# Amplifier2ch.net
KiCad netlist of a schematic drawn in Altium Designer
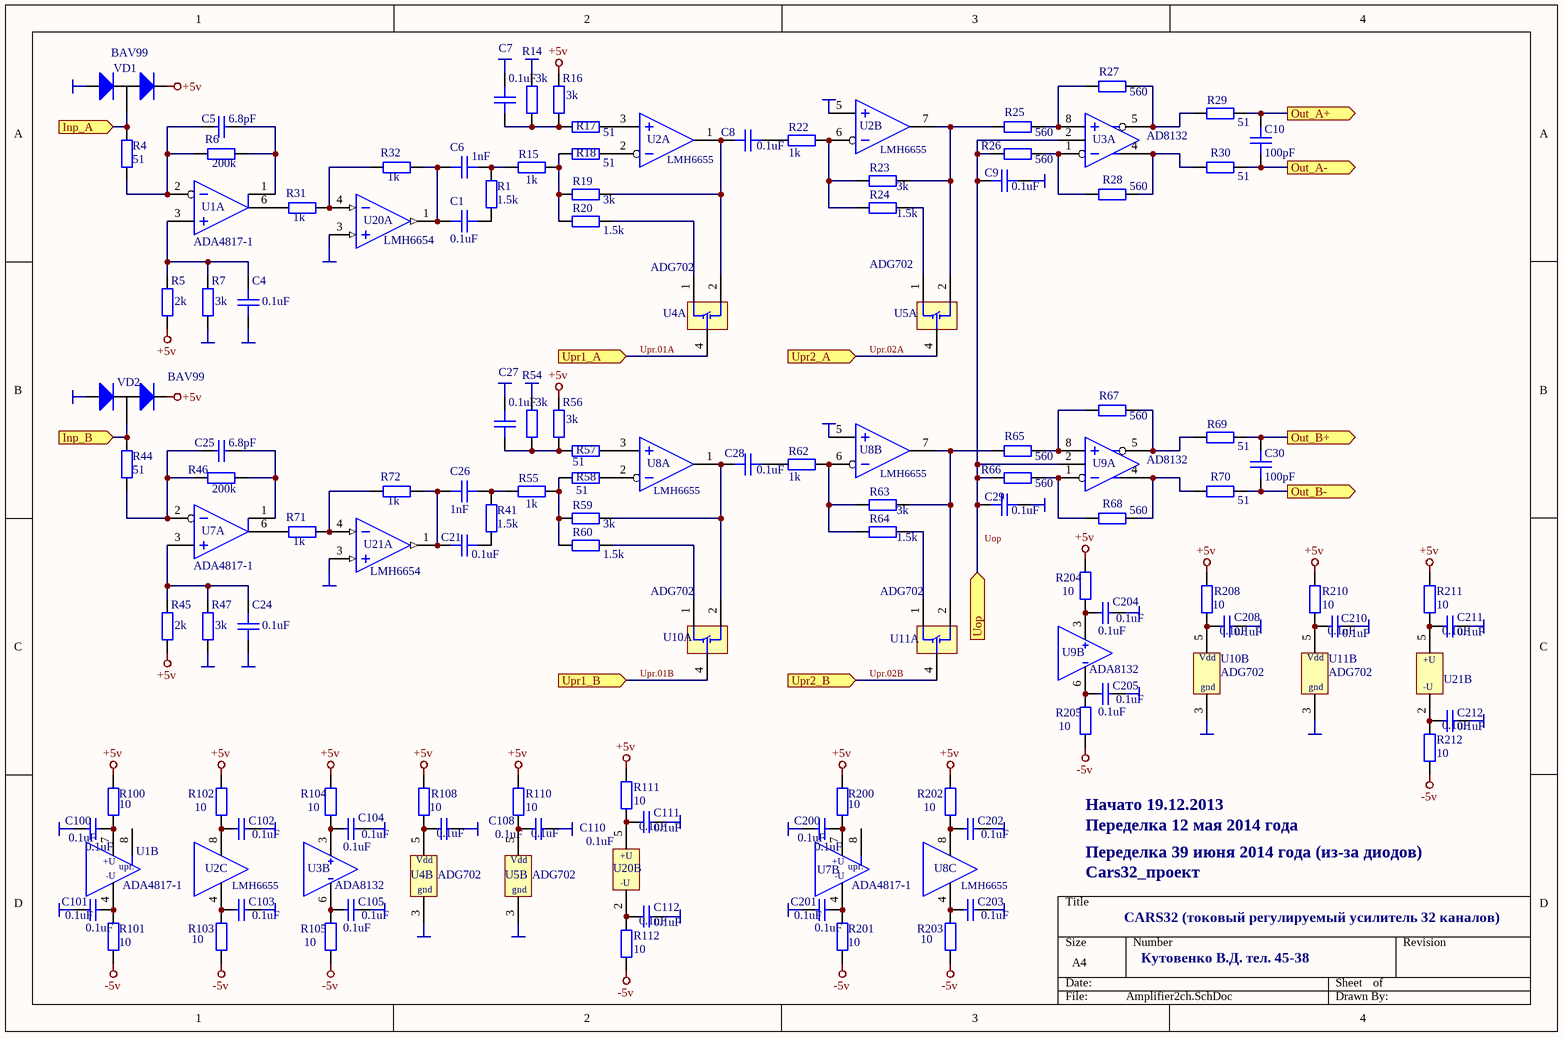
[diagram p0: Amplifier2ch.SchDoc]

(export (version "E")
  (design (tool "Eeschema 10.0.6"))
  (components
    (comp (ref "C1") (value "0.1uF") (footprint "0603") (libsource (lib "Kut") (part "C")))
    (comp (ref "C4") (value "0.1uF") (footprint "0603") (libsource (lib "Kut") (part "C")))
    (comp (ref "C5")
      (value "6.8pF")
      (footprint "0603")
      (description "Capacitor")
      (fields (field (name "PUBLISHER") "Altium Limited"))
      (libsource (lib "Miscellaneous Devices") (part "Cap"))
    )
    (comp (ref "C6") (value "1nF") (footprint "0603") (libsource (lib "Kut") (part "C")))
    (comp (ref "C7") (value "0.1uF") (footprint "0603") (libsource (lib "Kut") (part "C")))
    (comp (ref "C8") (value "0.1uF") (footprint "0603") (libsource (lib "Kut") (part "C")))
    (comp (ref "C9") (value "0.1uF") (footprint "0603") (libsource (lib "Kut") (part "C")))
    (comp (ref "C10") (value "100pF") (footprint "0603") (libsource (lib "Kut") (part "C")))
    (comp (ref "C21") (value "0.1uF") (footprint "0603") (libsource (lib "Kut") (part "C")))
    (comp (ref "C24") (value "0.1uF") (footprint "0603") (libsource (lib "Kut") (part "C")))
    (comp (ref "C25")
      (value "6.8pF")
      (footprint "0603")
      (description "Capacitor")
      (fields (field (name "PUBLISHER") "Altium Limited"))
      (libsource (lib "Miscellaneous Devices") (part "Cap"))
    )
    (comp (ref "C26") (value "1nF") (footprint "0603") (libsource (lib "Kut") (part "C")))
    (comp (ref "C27") (value "0.1uF") (footprint "0603") (libsource (lib "Kut") (part "C")))
    (comp (ref "C28") (value "0.1uF") (footprint "0603") (libsource (lib "Kut") (part "C")))
    (comp (ref "C29") (value "0.1uF") (footprint "0603") (libsource (lib "Kut") (part "C")))
    (comp (ref "C30") (value "100pF") (footprint "0603") (libsource (lib "Kut") (part "C")))
    (comp (ref "C100")
      (value "0.1uF")
      (footprint "0603")
      (description "Capacitor")
      (fields (field (name "ALTIUM_VALUE") "0.1uF") (field (name "PUBLISHER") "Altium Limited"))
      (libsource (lib "Miscellaneous Devices") (part "Cap"))
    )
    (comp (ref "C101")
      (value "0.1uF")
      (footprint "0603")
      (description "Capacitor")
      (fields (field (name "ALTIUM_VALUE") "0.1uF") (field (name "PUBLISHER") "Altium Limited"))
      (libsource (lib "Miscellaneous Devices") (part "Cap"))
    )
    (comp (ref "C102")
      (value "0.1uF")
      (footprint "0603")
      (description "Capacitor")
      (fields (field (name "PUBLISHER") "Altium Limited"))
      (libsource (lib "Miscellaneous Devices") (part "Cap"))
    )
    (comp (ref "C103")
      (value "0.1uF")
      (footprint "0603")
      (description "Capacitor")
      (fields (field (name "PUBLISHER") "Altium Limited"))
      (libsource (lib "Miscellaneous Devices") (part "Cap"))
    )
    (comp (ref "C104")
      (value "0.1uF")
      (footprint "0603")
      (description "Capacitor")
      (fields (field (name "ALTIUM_VALUE") "0.1uF") (field (name "PUBLISHER") "Altium Limited"))
      (libsource (lib "Miscellaneous Devices") (part "Cap"))
    )
    (comp (ref "C105")
      (value "0.1uF")
      (footprint "0603")
      (description "Capacitor")
      (fields (field (name "ALTIUM_VALUE") "0.1uF") (field (name "PUBLISHER") "Altium Limited"))
      (libsource (lib "Miscellaneous Devices") (part "Cap"))
    )
    (comp (ref "C108")
      (value "0.1uF")
      (footprint "0603")
      (description "Capacitor")
      (fields (field (name "ALTIUM_VALUE") "0.1uF") (field (name "PUBLISHER") "Altium Limited"))
      (libsource (lib "Miscellaneous Devices") (part "Cap"))
    )
    (comp (ref "C110")
      (value "0.1uF")
      (footprint "0603")
      (description "Capacitor")
      (fields (field (name "ALTIUM_VALUE") "0.1uF") (field (name "PUBLISHER") "Altium Limited"))
      (libsource (lib "Miscellaneous Devices") (part "Cap"))
    )
    (comp (ref "C111")
      (value "0.1uF")
      (footprint "0603")
      (description "Capacitor")
      (fields (field (name "ALTIUM_VALUE") "0.1uF") (field (name "PUBLISHER") "Altium Limited"))
      (libsource (lib "Miscellaneous Devices") (part "Cap"))
    )
    (comp (ref "C112")
      (value "0.1uF")
      (footprint "0603")
      (description "Capacitor")
      (fields (field (name "ALTIUM_VALUE") "0.1uF") (field (name "PUBLISHER") "Altium Limited"))
      (libsource (lib "Miscellaneous Devices") (part "Cap"))
    )
    (comp (ref "C200")
      (value "0.1uF")
      (footprint "0603")
      (description "Capacitor")
      (fields (field (name "ALTIUM_VALUE") "0.1uF") (field (name "PUBLISHER") "Altium Limited"))
      (libsource (lib "Miscellaneous Devices") (part "Cap"))
    )
    (comp (ref "C201")
      (value "0.1uF")
      (footprint "0603")
      (description "Capacitor")
      (fields (field (name "ALTIUM_VALUE") "0.1uF") (field (name "PUBLISHER") "Altium Limited"))
      (libsource (lib "Miscellaneous Devices") (part "Cap"))
    )
    (comp (ref "C202")
      (value "0.1uF")
      (footprint "0603")
      (description "Capacitor")
      (fields (field (name "PUBLISHER") "Altium Limited"))
      (libsource (lib "Miscellaneous Devices") (part "Cap"))
    )
    (comp (ref "C203")
      (value "0.1uF")
      (footprint "0603")
      (description "Capacitor")
      (fields (field (name "PUBLISHER") "Altium Limited"))
      (libsource (lib "Miscellaneous Devices") (part "Cap"))
    )
    (comp (ref "C204")
      (value "0.1uF")
      (footprint "0603")
      (description "Capacitor")
      (fields (field (name "ALTIUM_VALUE") "0.1uF") (field (name "PUBLISHER") "Altium Limited"))
      (libsource (lib "Miscellaneous Devices") (part "Cap"))
    )
    (comp (ref "C205")
      (value "0.1uF")
      (footprint "0603")
      (description "Capacitor")
      (fields (field (name "ALTIUM_VALUE") "0.1uF") (field (name "PUBLISHER") "Altium Limited"))
      (libsource (lib "Miscellaneous Devices") (part "Cap"))
    )
    (comp (ref "C208")
      (value "0.1uF")
      (footprint "0603")
      (description "Capacitor")
      (fields (field (name "ALTIUM_VALUE") "0.1uF") (field (name "PUBLISHER") "Altium Limited"))
      (libsource (lib "Miscellaneous Devices") (part "Cap"))
    )
    (comp (ref "C210")
      (value "0.1uF")
      (footprint "0603")
      (description "Capacitor")
      (fields (field (name "ALTIUM_VALUE") "0.1uF") (field (name "PUBLISHER") "Altium Limited"))
      (libsource (lib "Miscellaneous Devices") (part "Cap"))
    )
    (comp (ref "C211")
      (value "0.1uF")
      (footprint "0603")
      (description "Capacitor")
      (fields (field (name "ALTIUM_VALUE") "0.1uF") (field (name "PUBLISHER") "Altium Limited"))
      (libsource (lib "Miscellaneous Devices") (part "Cap"))
    )
    (comp (ref "C212")
      (value "0.1uF")
      (footprint "0603")
      (description "Capacitor")
      (fields (field (name "ALTIUM_VALUE") "0.1uF") (field (name "PUBLISHER") "Altium Limited"))
      (libsource (lib "Miscellaneous Devices") (part "Cap"))
    )
    (comp (ref "R1")
      (value "1.5k")
      (footprint "0603")
      (description "Resistor")
      (fields (field (name "PUBLISHER") "Altium Limited"))
      (libsource (lib "") (part "Res2_2"))
    )
    (comp (ref "R4")
      (value "51")
      (footprint "0603")
      (description "Resistor")
      (fields (field (name "PUBLISHER") "Altium Limited"))
      (libsource (lib "") (part "Res2_2"))
    )
    (comp (ref "R5")
      (value "2k")
      (footprint "0603")
      (description "Resistor")
      (fields (field (name "PUBLISHER") "Altium Limited"))
      (libsource (lib "") (part "Res2_2"))
    )
    (comp (ref "R6")
      (value "200k")
      (footprint "0603")
      (description "Resistor")
      (fields (field (name "PUBLISHER") "Altium Limited"))
      (libsource (lib "Miscellaneous Devices") (part "Res2"))
    )
    (comp (ref "R7")
      (value "3k")
      (footprint "0603")
      (description "Resistor")
      (fields (field (name "PUBLISHER") "Altium Limited"))
      (libsource (lib "") (part "Res2_1"))
    )
    (comp (ref "R14")
      (value "3k")
      (footprint "0603")
      (description "Resistor")
      (fields (field (name "PUBLISHER") "Altium Limited"))
      (libsource (lib "") (part "Res2_1"))
    )
    (comp (ref "R15")
      (value "1k")
      (footprint "0603")
      (description "Resistor")
      (fields (field (name "PUBLISHER") "Altium Limited"))
      (libsource (lib "Miscellaneous Devices") (part "Res2"))
    )
    (comp (ref "R16")
      (value "3k")
      (footprint "0603")
      (description "Resistor")
      (fields (field (name "PUBLISHER") "Altium Limited"))
      (libsource (lib "") (part "Res2_1"))
    )
    (comp (ref "R17")
      (value "51")
      (footprint "0603")
      (description "Resistor")
      (fields (field (name "PUBLISHER") "Altium Limited"))
      (libsource (lib "Miscellaneous Devices") (part "Res2"))
    )
    (comp (ref "R18")
      (value "51")
      (footprint "0603")
      (description "Resistor")
      (fields (field (name "PUBLISHER") "Altium Limited"))
      (libsource (lib "Miscellaneous Devices") (part "Res2"))
    )
    (comp (ref "R19")
      (value "3k")
      (footprint "0603")
      (description "Resistor")
      (fields (field (name "PUBLISHER") "Altium Limited"))
      (libsource (lib "Miscellaneous Devices") (part "Res2"))
    )
    (comp (ref "R20")
      (value "1.5k")
      (footprint "0603")
      (description "Resistor")
      (fields (field (name "PUBLISHER") "Altium Limited"))
      (libsource (lib "Miscellaneous Devices") (part "Res2"))
    )
    (comp (ref "R22")
      (value "1k")
      (footprint "0603")
      (description "Resistor")
      (fields (field (name "PUBLISHER") "Altium Limited"))
      (libsource (lib "Miscellaneous Devices") (part "Res2"))
    )
    (comp (ref "R23")
      (value "3k")
      (footprint "0603")
      (description "Resistor")
      (fields (field (name "PUBLISHER") "Altium Limited"))
      (libsource (lib "Miscellaneous Devices") (part "Res2"))
    )
    (comp (ref "R24")
      (value "1.5k")
      (footprint "0603")
      (description "Resistor")
      (fields (field (name "PUBLISHER") "Altium Limited"))
      (libsource (lib "Miscellaneous Devices") (part "Res2"))
    )
    (comp (ref "R25")
      (value "560")
      (footprint "0603")
      (description "Resistor")
      (fields (field (name "PUBLISHER") "Altium Limited"))
      (libsource (lib "Miscellaneous Devices") (part "Res2"))
    )
    (comp (ref "R26")
      (value "560")
      (footprint "0603")
      (description "Resistor")
      (fields (field (name "PUBLISHER") "Altium Limited"))
      (libsource (lib "Miscellaneous Devices") (part "Res2"))
    )
    (comp (ref "R27")
      (value "560")
      (footprint "0603")
      (description "Resistor")
      (fields (field (name "PUBLISHER") "Altium Limited"))
      (libsource (lib "Miscellaneous Devices") (part "Res2"))
    )
    (comp (ref "R28")
      (value "560")
      (footprint "0603")
      (description "Resistor")
      (fields (field (name "PUBLISHER") "Altium Limited"))
      (libsource (lib "Miscellaneous Devices") (part "Res2"))
    )
    (comp (ref "R29")
      (value "51")
      (footprint "0603")
      (description "Resistor")
      (fields (field (name "PUBLISHER") "Altium Limited"))
      (libsource (lib "Miscellaneous Devices") (part "Res2"))
    )
    (comp (ref "R30")
      (value "51")
      (footprint "0603")
      (description "Resistor")
      (fields (field (name "PUBLISHER") "Altium Limited"))
      (libsource (lib "Miscellaneous Devices") (part "Res2"))
    )
    (comp (ref "R31")
      (value "1k")
      (footprint "0603")
      (description "Resistor")
      (fields (field (name "PUBLISHER") "Altium Limited"))
      (libsource (lib "Miscellaneous Devices") (part "Res2"))
    )
    (comp (ref "R32")
      (value "1k")
      (footprint "0603")
      (description "Resistor")
      (fields (field (name "PUBLISHER") "Altium Limited"))
      (libsource (lib "Miscellaneous Devices") (part "Res2"))
    )
    (comp (ref "R41")
      (value "1.5k")
      (footprint "0603")
      (description "Resistor")
      (fields (field (name "PUBLISHER") "Altium Limited"))
      (libsource (lib "") (part "Res2_1"))
    )
    (comp (ref "R44")
      (value "51")
      (footprint "0603")
      (description "Resistor")
      (fields (field (name "PUBLISHER") "Altium Limited"))
      (libsource (lib "") (part "Res2_1"))
    )
    (comp (ref "R45")
      (value "2k")
      (footprint "0603")
      (description "Resistor")
      (fields (field (name "PUBLISHER") "Altium Limited"))
      (libsource (lib "") (part "Res2_2"))
    )
    (comp (ref "R46")
      (value "200k")
      (footprint "0603")
      (description "Resistor")
      (fields (field (name "PUBLISHER") "Altium Limited"))
      (libsource (lib "Miscellaneous Devices") (part "Res2"))
    )
    (comp (ref "R47")
      (value "3k")
      (footprint "0603")
      (description "Resistor")
      (fields (field (name "PUBLISHER") "Altium Limited"))
      (libsource (lib "") (part "Res2_1"))
    )
    (comp (ref "R54")
      (value "3k")
      (footprint "0603")
      (description "Resistor")
      (fields (field (name "PUBLISHER") "Altium Limited"))
      (libsource (lib "") (part "Res2_1"))
    )
    (comp (ref "R55")
      (value "1k")
      (footprint "0603")
      (description "Resistor")
      (fields (field (name "PUBLISHER") "Altium Limited"))
      (libsource (lib "Miscellaneous Devices") (part "Res2"))
    )
    (comp (ref "R56")
      (value "3k")
      (footprint "0603")
      (description "Resistor")
      (fields (field (name "PUBLISHER") "Altium Limited"))
      (libsource (lib "") (part "Res2_1"))
    )
    (comp (ref "R57")
      (value "51")
      (footprint "0603")
      (description "Resistor")
      (fields (field (name "PUBLISHER") "Altium Limited"))
      (libsource (lib "") (part "Res2_3"))
    )
    (comp (ref "R58")
      (value "51")
      (footprint "0603")
      (description "Resistor")
      (fields (field (name "PUBLISHER") "Altium Limited"))
      (libsource (lib "Miscellaneous Devices") (part "Res2"))
    )
    (comp (ref "R59")
      (value "3k")
      (footprint "0603")
      (description "Resistor")
      (fields (field (name "PUBLISHER") "Altium Limited"))
      (libsource (lib "Miscellaneous Devices") (part "Res2"))
    )
    (comp (ref "R60")
      (value "1.5k")
      (footprint "0603")
      (description "Resistor")
      (fields (field (name "PUBLISHER") "Altium Limited"))
      (libsource (lib "Miscellaneous Devices") (part "Res2"))
    )
    (comp (ref "R62")
      (value "1k")
      (footprint "0603")
      (description "Resistor")
      (fields (field (name "PUBLISHER") "Altium Limited"))
      (libsource (lib "Miscellaneous Devices") (part "Res2"))
    )
    (comp (ref "R63")
      (value "3k")
      (footprint "0603")
      (description "Resistor")
      (fields (field (name "PUBLISHER") "Altium Limited"))
      (libsource (lib "Miscellaneous Devices") (part "Res2"))
    )
    (comp (ref "R64")
      (value "1.5k")
      (footprint "0603")
      (description "Resistor")
      (fields (field (name "PUBLISHER") "Altium Limited"))
      (libsource (lib "Miscellaneous Devices") (part "Res2"))
    )
    (comp (ref "R65")
      (value "560")
      (footprint "0603")
      (description "Resistor")
      (fields (field (name "PUBLISHER") "Altium Limited"))
      (libsource (lib "Miscellaneous Devices") (part "Res2"))
    )
    (comp (ref "R66")
      (value "560")
      (footprint "0603")
      (description "Resistor")
      (fields (field (name "PUBLISHER") "Altium Limited"))
      (libsource (lib "Miscellaneous Devices") (part "Res2"))
    )
    (comp (ref "R67")
      (value "560")
      (footprint "0603")
      (description "Resistor")
      (fields (field (name "PUBLISHER") "Altium Limited"))
      (libsource (lib "Miscellaneous Devices") (part "Res2"))
    )
    (comp (ref "R68")
      (value "560")
      (footprint "0603")
      (description "Resistor")
      (fields (field (name "PUBLISHER") "Altium Limited"))
      (libsource (lib "Miscellaneous Devices") (part "Res2"))
    )
    (comp (ref "R69")
      (value "51")
      (footprint "0603")
      (description "Resistor")
      (fields (field (name "PUBLISHER") "Altium Limited"))
      (libsource (lib "Miscellaneous Devices") (part "Res2"))
    )
    (comp (ref "R70")
      (value "51")
      (footprint "0603")
      (description "Resistor")
      (fields (field (name "PUBLISHER") "Altium Limited"))
      (libsource (lib "Miscellaneous Devices") (part "Res2"))
    )
    (comp (ref "R71")
      (value "1k")
      (footprint "0603")
      (description "Resistor")
      (fields (field (name "PUBLISHER") "Altium Limited"))
      (libsource (lib "Miscellaneous Devices") (part "Res2"))
    )
    (comp (ref "R72")
      (value "1k")
      (footprint "0603")
      (description "Resistor")
      (fields (field (name "PUBLISHER") "Altium Limited"))
      (libsource (lib "Miscellaneous Devices") (part "Res2"))
    )
    (comp (ref "R100")
      (value "10")
      (footprint "0603")
      (description "Resistor")
      (fields (field (name "PUBLISHER") "Altium Limited"))
      (libsource (lib "") (part "Res2_1"))
    )
    (comp (ref "R101")
      (value "10")
      (footprint "0603")
      (description "Resistor")
      (fields (field (name "PUBLISHER") "Altium Limited"))
      (libsource (lib "") (part "Res2_1"))
    )
    (comp (ref "R102")
      (value "10")
      (footprint "0603")
      (description "Resistor")
      (fields (field (name "PUBLISHER") "Altium Limited"))
      (libsource (lib "") (part "Res2_1"))
    )
    (comp (ref "R103")
      (value "10")
      (footprint "0603")
      (description "Resistor")
      (fields (field (name "PUBLISHER") "Altium Limited"))
      (libsource (lib "") (part "Res2_1"))
    )
    (comp (ref "R104")
      (value "10")
      (footprint "0603")
      (description "Resistor")
      (fields (field (name "PUBLISHER") "Altium Limited"))
      (libsource (lib "") (part "Res2_1"))
    )
    (comp (ref "R105")
      (value "10")
      (footprint "0603")
      (description "Resistor")
      (fields (field (name "PUBLISHER") "Altium Limited"))
      (libsource (lib "") (part "Res2_1"))
    )
    (comp (ref "R108")
      (value "10")
      (footprint "0603")
      (description "Resistor")
      (fields (field (name "PUBLISHER") "Altium Limited"))
      (libsource (lib "") (part "Res2_1"))
    )
    (comp (ref "R110")
      (value "10")
      (footprint "0603")
      (description "Resistor")
      (fields (field (name "PUBLISHER") "Altium Limited"))
      (libsource (lib "") (part "Res2_1"))
    )
    (comp (ref "R111")
      (value "10")
      (footprint "0603")
      (description "Resistor")
      (fields (field (name "PUBLISHER") "Altium Limited"))
      (libsource (lib "") (part "Res2_1"))
    )
    (comp (ref "R112")
      (value "10")
      (footprint "0603")
      (description "Resistor")
      (fields (field (name "PUBLISHER") "Altium Limited"))
      (libsource (lib "") (part "Res2_1"))
    )
    (comp (ref "R200")
      (value "10")
      (footprint "0603")
      (description "Resistor")
      (fields (field (name "PUBLISHER") "Altium Limited"))
      (libsource (lib "") (part "Res2_1"))
    )
    (comp (ref "R201")
      (value "10")
      (footprint "0603")
      (description "Resistor")
      (fields (field (name "PUBLISHER") "Altium Limited"))
      (libsource (lib "") (part "Res2_1"))
    )
    (comp (ref "R202")
      (value "10")
      (footprint "0603")
      (description "Resistor")
      (fields (field (name "PUBLISHER") "Altium Limited"))
      (libsource (lib "") (part "Res2_1"))
    )
    (comp (ref "R203")
      (value "10")
      (footprint "0603")
      (description "Resistor")
      (fields (field (name "PUBLISHER") "Altium Limited"))
      (libsource (lib "") (part "Res2_1"))
    )
    (comp (ref "R204")
      (value "10")
      (footprint "0603")
      (description "Resistor")
      (fields (field (name "PUBLISHER") "Altium Limited"))
      (libsource (lib "") (part "Res2_1"))
    )
    (comp (ref "R205")
      (value "10")
      (footprint "0603")
      (description "Resistor")
      (fields (field (name "PUBLISHER") "Altium Limited"))
      (libsource (lib "") (part "Res2_1"))
    )
    (comp (ref "R208")
      (value "10")
      (footprint "0603")
      (description "Resistor")
      (fields (field (name "PUBLISHER") "Altium Limited"))
      (libsource (lib "") (part "Res2_1"))
    )
    (comp (ref "R210")
      (value "10")
      (footprint "0603")
      (description "Resistor")
      (fields (field (name "PUBLISHER") "Altium Limited"))
      (libsource (lib "") (part "Res2_1"))
    )
    (comp (ref "R211")
      (value "10")
      (footprint "0603")
      (description "Resistor")
      (fields (field (name "PUBLISHER") "Altium Limited"))
      (libsource (lib "") (part "Res2_1"))
    )
    (comp (ref "R212")
      (value "10")
      (footprint "0603")
      (description "Resistor")
      (fields (field (name "PUBLISHER") "Altium Limited"))
      (libsource (lib "") (part "Res2_1"))
    )
    (comp (ref "U1") (value "ADA4817-1") (footprint "8SOIC150") (libsource (lib "Kut") (part "ADA4817-1")))
    (comp (ref "U2") (value "LMH6655") (footprint "8SOIC150") (libsource (lib "Kut") (part "LMH6655")))
    (comp (ref "U3")
      (value "AD8132")
      (footprint "8SOIC150")
      (fields (field (name "Comment") "AD8132") (field (name "PUBLISHER") "Altium Limited"))
      (libsource (lib "Kut") (part "AD8132"))
    )
    (comp (ref "U4") (value "ADG702") (footprint "SOT-23-5") (libsource (lib "Kut") (part "ADG702")))
    (comp (ref "U5") (value "ADG702") (footprint "SOT-23-5") (libsource (lib "Kut") (part "ADG702")))
    (comp (ref "U7") (value "ADA4817-1") (footprint "8SOIC150") (libsource (lib "Kut") (part "ADA4817-1")))
    (comp (ref "U8") (value "LMH6655") (footprint "8SOIC150") (libsource (lib "Kut") (part "LMH6655")))
    (comp (ref "U9")
      (value "ADA8132")
      (footprint "AD8132")
      (fields (field (name "Comment") "AD8132") (field (name "PUBLISHER") "Altium Limited"))
      (libsource (lib "PreampAul2") (part "AD8132"))
    )
    (comp (ref "U10") (value "ADG702") (footprint "SOT-23-5") (libsource (lib "") (part "ADG702_1")))
    (comp (ref "U11") (value "ADG702") (footprint "SOT-23-5") (libsource (lib "") (part "ADG702_1")))
    (comp (ref "U20") (value "LMH6654") (footprint "SOT-23-5") (libsource (lib "Kut") (part "LMH6654")))
    (comp (ref "U21") (value "LMH6654") (footprint "SOT-23-5") (libsource (lib "Kut") (part "LMH6654")))
    (comp (ref "VD1") (value "BAV99") (footprint "SOT-23") (libsource (lib "Kut") (part "BAV99")))
    (comp (ref "VD2") (value "BAV99") (footprint "SOT-23") (libsource (lib "Kut") (part "BAV99")))
  )
  (nets
    (net (code "1") (name "+5v") (class "Default")
      (node (ref "R100") (pin "2") (pinfunction "2_2") (pintype "passive"))
      (node (ref "R102") (pin "2") (pinfunction "2_2") (pintype "passive"))
      (node (ref "R104") (pin "2") (pinfunction "2_2") (pintype "passive"))
      (node (ref "R108") (pin "2") (pinfunction "2_2") (pintype "passive"))
      (node (ref "R110") (pin "2") (pinfunction "2_2") (pintype "passive"))
      (node (ref "R111") (pin "2") (pinfunction "2_2") (pintype "passive"))
      (node (ref "R16") (pin "2") (pinfunction "2_2") (pintype "passive"))
      (node (ref "R200") (pin "2") (pinfunction "2_2") (pintype "passive"))
      (node (ref "R202") (pin "2") (pinfunction "2_2") (pintype "passive"))
      (node (ref "R204") (pin "2") (pinfunction "2_2") (pintype "passive"))
      (node (ref "R208") (pin "2") (pinfunction "2_2") (pintype "passive"))
      (node (ref "R210") (pin "2") (pinfunction "2_2") (pintype "passive"))
      (node (ref "R211") (pin "2") (pinfunction "2_2") (pintype "passive"))
      (node (ref "R45") (pin "2") (pinfunction "2_2") (pintype "passive"))
      (node (ref "R5") (pin "2") (pinfunction "2_2") (pintype "passive"))
      (node (ref "R56") (pin "2") (pinfunction "2_2") (pintype "passive"))
      (node (ref "VD1") (pin "2") (pinfunction "K_2") (pintype "passive"))
      (node (ref "VD2") (pin "2") (pinfunction "K_2") (pintype "passive"))
    )
    (net (code "2") (name "-5v") (class "Default")
      (node (ref "R101") (pin "1") (pinfunction "1_1") (pintype "passive"))
      (node (ref "R103") (pin "1") (pinfunction "1_1") (pintype "passive"))
      (node (ref "R105") (pin "1") (pinfunction "1_1") (pintype "passive"))
      (node (ref "R112") (pin "1") (pinfunction "1_1") (pintype "passive"))
      (node (ref "R201") (pin "1") (pinfunction "1_1") (pintype "passive"))
      (node (ref "R203") (pin "1") (pinfunction "1_1") (pintype "passive"))
      (node (ref "R205") (pin "1") (pinfunction "1_1") (pintype "passive"))
      (node (ref "R212") (pin "1") (pinfunction "1_1") (pintype "passive"))
    )
    (net (code "3") (name "/Inp_A") (class "Default")
      (node (ref "R4") (pin "1") (pinfunction "1_1") (pintype "passive"))
      (node (ref "VD1") (pin "3") (pinfunction "C_3") (pintype "passive"))
    )
    (net (code "4") (name "/Inp_B") (class "Default")
      (node (ref "R44") (pin "2") (pinfunction "2_2") (pintype "passive"))
      (node (ref "VD2") (pin "3") (pinfunction "C_3") (pintype "passive"))
    )
    (net (code "5") (name "/Out_A+") (class "Default")
      (node (ref "C10") (pin "2") (pinfunction "2_2") (pintype "passive"))
      (node (ref "R29") (pin "2") (pinfunction "2_2") (pintype "passive"))
    )
    (net (code "6") (name "/Out_A-") (class "Default")
      (node (ref "C10") (pin "1") (pinfunction "1_1") (pintype "passive"))
      (node (ref "R30") (pin "2") (pinfunction "2_2") (pintype "passive"))
    )
    (net (code "7") (name "/Out_B+") (class "Default")
      (node (ref "C30") (pin "2") (pinfunction "2_2") (pintype "passive"))
      (node (ref "R69") (pin "2") (pinfunction "2_2") (pintype "passive"))
    )
    (net (code "8") (name "/Out_B-") (class "Default")
      (node (ref "C30") (pin "1") (pinfunction "1_1") (pintype "passive"))
      (node (ref "R70") (pin "2") (pinfunction "2_2") (pintype "passive"))
    )
    (net (code "9") (name "/Uop") (class "Default")
      (node (ref "C29") (pin "2") (pinfunction "2_2") (pintype "passive"))
      (node (ref "C9") (pin "2") (pinfunction "2_2") (pintype "passive"))
      (node (ref "R26") (pin "1") (pinfunction "1_1") (pintype "passive"))
      (node (ref "R66") (pin "1") (pinfunction "1_1") (pintype "passive"))
      (node (ref "U3") (pin "2") (pinfunction "2_2") (pintype "passive"))
      (node (ref "U9") (pin "2") (pinfunction "2_2") (pintype "passive"))
    )
    (net (code "10") (name "/Upr.01A") (class "Default")
      (node (ref "U4") (pin "4") (pinfunction "IN_4") (pintype "passive"))
    )
    (net (code "11") (name "/Upr.01B") (class "Default")
      (node (ref "U10") (pin "4") (pinfunction "IN_4") (pintype "passive"))
    )
    (net (code "12") (name "/Upr.02A") (class "Default")
      (node (ref "U5") (pin "4") (pinfunction "IN_4") (pintype "passive"))
    )
    (net (code "13") (name "/Upr.02B") (class "Default")
      (node (ref "U11") (pin "4") (pinfunction "IN_4") (pintype "passive"))
    )
    (net (code "14") (name "AGND") (class "Default")
      (node (ref "C24") (pin "1") (pinfunction "1_1") (pintype "passive"))
      (node (ref "C27") (pin "2") (pinfunction "2_2") (pintype "passive"))
      (node (ref "C29") (pin "1") (pinfunction "1_1") (pintype "passive"))
      (node (ref "C4") (pin "1") (pinfunction "1_1") (pintype "passive"))
      (node (ref "C7") (pin "2") (pinfunction "2_2") (pintype "passive"))
      (node (ref "C9") (pin "1") (pinfunction "1_1") (pintype "passive"))
      (node (ref "R14") (pin "2") (pinfunction "2_2") (pintype "passive"))
      (node (ref "R47") (pin "1") (pinfunction "1_1") (pintype "passive"))
      (node (ref "R54") (pin "2") (pinfunction "2_2") (pintype "passive"))
      (node (ref "R7") (pin "1") (pinfunction "1_1") (pintype "passive"))
      (node (ref "U2") (pin "5") (pinfunction "IN+_5") (pintype "passive"))
      (node (ref "U20") (pin "3") (pinfunction "IN+_3") (pintype "input"))
      (node (ref "U21") (pin "3") (pinfunction "IN+_3") (pintype "input"))
      (node (ref "U8") (pin "5") (pinfunction "IN+_5") (pintype "passive"))
      (node (ref "VD1") (pin "1") (pinfunction "A_1") (pintype "passive"))
      (node (ref "VD2") (pin "1") (pinfunction "A_1") (pintype "passive"))
    )
    (net (code "15") (name "GND") (class "Default")
      (node (ref "C100") (pin "1") (pinfunction "1_1") (pintype "passive"))
      (node (ref "C101") (pin "1") (pinfunction "1_1") (pintype "passive"))
      (node (ref "C102") (pin "2") (pinfunction "2_2") (pintype "passive"))
      (node (ref "C103") (pin "2") (pinfunction "2_2") (pintype "passive"))
      (node (ref "C104") (pin "2") (pinfunction "2_2") (pintype "passive"))
      (node (ref "C105") (pin "2") (pinfunction "2_2") (pintype "passive"))
      (node (ref "C108") (pin "1") (pinfunction "1_1") (pintype "passive"))
      (node (ref "C110") (pin "1") (pinfunction "1_1") (pintype "passive"))
      (node (ref "C111") (pin "1") (pinfunction "1_1") (pintype "passive"))
      (node (ref "C112") (pin "1") (pinfunction "1_1") (pintype "passive"))
      (node (ref "C200") (pin "1") (pinfunction "1_1") (pintype "passive"))
      (node (ref "C201") (pin "1") (pinfunction "1_1") (pintype "passive"))
      (node (ref "C202") (pin "2") (pinfunction "2_2") (pintype "passive"))
      (node (ref "C203") (pin "2") (pinfunction "2_2") (pintype "passive"))
      (node (ref "C204") (pin "2") (pinfunction "2_2") (pintype "passive"))
      (node (ref "C205") (pin "2") (pinfunction "2_2") (pintype "passive"))
      (node (ref "C208") (pin "1") (pinfunction "1_1") (pintype "passive"))
      (node (ref "C210") (pin "1") (pinfunction "1_1") (pintype "passive"))
      (node (ref "C211") (pin "1") (pinfunction "1_1") (pintype "passive"))
      (node (ref "C212") (pin "1") (pinfunction "1_1") (pintype "passive"))
      (node (ref "U10") (pin "3") (pinfunction "GND_3") (pintype "passive"))
      (node (ref "U11") (pin "3") (pinfunction "GND_3") (pintype "passive"))
      (node (ref "U4") (pin "3") (pinfunction "GND_3") (pintype "passive"))
      (node (ref "U5") (pin "3") (pinfunction "GND_3") (pintype "passive"))
    )
    (net (code "16") (name "Net-(C1-Pad1)") (class "Default")
      (node (ref "C1") (pin "1") (pinfunction "1_1") (pintype "passive"))
      (node (ref "R1") (pin "2") (pinfunction "2_2") (pintype "passive"))
    )
    (net (code "17") (name "Net-(C5-Pad2)") (class "Default")
      (node (ref "C5") (pin "2") (pinfunction "2_2") (pintype "passive"))
      (node (ref "R6") (pin "2") (pinfunction "2_2") (pintype "passive"))
      (node (ref "U1") (pin "1") (pinfunction "1_1") (pintype "passive"))
    )
    (net (code "18") (name "Net-(C6-Pad1)") (class "Default")
      (node (ref "C6") (pin "1") (pinfunction "1_1") (pintype "passive"))
      (node (ref "R1") (pin "1") (pinfunction "1_1") (pintype "passive"))
      (node (ref "R15") (pin "1") (pinfunction "1_1") (pintype "passive"))
    )
    (net (code "19") (name "Net-(C7-Pad1)") (class "Default")
      (node (ref "C7") (pin "1") (pinfunction "1_1") (pintype "passive"))
      (node (ref "R14") (pin "1") (pinfunction "1_1") (pintype "passive"))
      (node (ref "R16") (pin "1") (pinfunction "1_1") (pintype "passive"))
      (node (ref "R17") (pin "1") (pinfunction "1_1") (pintype "passive"))
    )
    (net (code "20") (name "Net-(C8-Pad2)") (class "Default")
      (node (ref "C8") (pin "2") (pinfunction "2_2") (pintype "passive"))
      (node (ref "R22") (pin "1") (pinfunction "1_1") (pintype "passive"))
    )
    (net (code "21") (name "Net-(C21-Pad2)") (class "Default")
      (node (ref "C21") (pin "2") (pinfunction "2_2") (pintype "passive"))
      (node (ref "R41") (pin "1") (pinfunction "1_1") (pintype "passive"))
    )
    (net (code "22") (name "Net-(C25-Pad2)") (class "Default")
      (node (ref "C25") (pin "2") (pinfunction "2_2") (pintype "passive"))
      (node (ref "R46") (pin "2") (pinfunction "2_2") (pintype "passive"))
      (node (ref "U7") (pin "1") (pinfunction "1_1") (pintype "passive"))
    )
    (net (code "23") (name "Net-(C26-Pad2)") (class "Default")
      (node (ref "C26") (pin "2") (pinfunction "2_2") (pintype "passive"))
      (node (ref "R41") (pin "2") (pinfunction "2_2") (pintype "passive"))
      (node (ref "R55") (pin "1") (pinfunction "1_1") (pintype "passive"))
    )
    (net (code "24") (name "Net-(C27-Pad1)") (class "Default")
      (node (ref "C27") (pin "1") (pinfunction "1_1") (pintype "passive"))
      (node (ref "R54") (pin "1") (pinfunction "1_1") (pintype "passive"))
      (node (ref "R56") (pin "1") (pinfunction "1_1") (pintype "passive"))
      (node (ref "R57") (pin "2") (pinfunction "2_2") (pintype "passive"))
    )
    (net (code "25") (name "Net-(C28-Pad2)") (class "Default")
      (node (ref "C28") (pin "2") (pinfunction "2_2") (pintype "passive"))
      (node (ref "R62") (pin "1") (pinfunction "1_1") (pintype "passive"))
    )
    (net (code "26") (name "Net-(R15-Pad2)") (class "Default")
      (node (ref "R15") (pin "2") (pinfunction "2_2") (pintype "passive"))
      (node (ref "R18") (pin "1") (pinfunction "1_1") (pintype "passive"))
      (node (ref "R19") (pin "1") (pinfunction "1_1") (pintype "passive"))
      (node (ref "R20") (pin "1") (pinfunction "1_1") (pintype "passive"))
    )
    (net (code "27") (name "Net-(R55-Pad2)") (class "Default")
      (node (ref "R55") (pin "2") (pinfunction "2_2") (pintype "passive"))
      (node (ref "R58") (pin "1") (pinfunction "1_1") (pintype "passive"))
      (node (ref "R59") (pin "1") (pinfunction "1_1") (pintype "passive"))
      (node (ref "R60") (pin "1") (pinfunction "1_1") (pintype "passive"))
    )
    (net (code "28") (name "Net-(U1A-IN+)") (class "Default")
      (node (ref "C4") (pin "2") (pinfunction "2_2") (pintype "passive"))
      (node (ref "R5") (pin "1") (pinfunction "1_1") (pintype "passive"))
      (node (ref "R7") (pin "2") (pinfunction "2_2") (pintype "passive"))
      (node (ref "U1") (pin "3") (pinfunction "IN+_3") (pintype "passive"))
    )
    (net (code "29") (name "Net-(U1A-IN-)") (class "Default")
      (node (ref "C5") (pin "1") (pinfunction "1_1") (pintype "passive"))
      (node (ref "R4") (pin "2") (pinfunction "2_2") (pintype "passive"))
      (node (ref "R6") (pin "1") (pinfunction "1_1") (pintype "passive"))
      (node (ref "U1") (pin "2") (pinfunction "IN-_2") (pintype "passive"))
    )
    (net (code "30") (name "Net-(U1A-OUT)") (class "Default")
      (node (ref "R31") (pin "1") (pinfunction "1_1") (pintype "passive"))
      (node (ref "U1") (pin "6") (pinfunction "OUT_6") (pintype "passive"))
    )
    (net (code "31") (name "Net-(U1B-V+)") (class "Default")
      (node (ref "C100") (pin "2") (pinfunction "2_2") (pintype "passive"))
      (node (ref "R100") (pin "1") (pinfunction "1_1") (pintype "passive"))
      (node (ref "U1") (pin "7") (pinfunction "V+_7") (pintype "passive"))
    )
    (net (code "32") (name "Net-(U1B-V-)") (class "Default")
      (node (ref "C101") (pin "2") (pinfunction "2_2") (pintype "passive"))
      (node (ref "R101") (pin "2") (pinfunction "2_2") (pintype "passive"))
      (node (ref "U1") (pin "4") (pinfunction "V-_4") (pintype "passive"))
    )
    (net (code "33") (name "Net-(U2A-IN+)") (class "Default")
      (node (ref "R17") (pin "2") (pinfunction "2_2") (pintype "passive"))
      (node (ref "U2") (pin "3") (pinfunction "IN+_3") (pintype "passive"))
    )
    (net (code "34") (name "Net-(U2A-IN-)") (class "Default")
      (node (ref "R18") (pin "2") (pinfunction "2_2") (pintype "passive"))
      (node (ref "U2") (pin "2") (pinfunction "IN-_2") (pintype "passive"))
    )
    (net (code "35") (name "Net-(U2A-OUT)") (class "Default")
      (node (ref "C8") (pin "1") (pinfunction "1_1") (pintype "passive"))
      (node (ref "R19") (pin "2") (pinfunction "2_2") (pintype "passive"))
      (node (ref "U2") (pin "1") (pinfunction "OUT_1") (pintype "passive"))
      (node (ref "U4") (pin "2") (pinfunction "S_2") (pintype "passive"))
    )
    (net (code "36") (name "Net-(U2B-IN-)") (class "Default")
      (node (ref "R22") (pin "2") (pinfunction "2_2") (pintype "passive"))
      (node (ref "R23") (pin "1") (pinfunction "1_1") (pintype "passive"))
      (node (ref "R24") (pin "1") (pinfunction "1_1") (pintype "passive"))
      (node (ref "U2") (pin "6") (pinfunction "IN-_6") (pintype "passive"))
    )
    (net (code "37") (name "Net-(U2B-OUT)") (class "Default")
      (node (ref "R23") (pin "2") (pinfunction "2_2") (pintype "passive"))
      (node (ref "R25") (pin "1") (pinfunction "1_1") (pintype "passive"))
      (node (ref "U2") (pin "7") (pinfunction "OUT_7") (pintype "passive"))
      (node (ref "U5") (pin "2") (pinfunction "S_2") (pintype "passive"))
    )
    (net (code "38") (name "Net-(U2C-V+)") (class "Default")
      (node (ref "C102") (pin "1") (pinfunction "1_1") (pintype "passive"))
      (node (ref "R102") (pin "1") (pinfunction "1_1") (pintype "passive"))
      (node (ref "U2") (pin "8") (pinfunction "V+_8") (pintype "passive"))
    )
    (net (code "39") (name "Net-(U2C-V-)") (class "Default")
      (node (ref "C103") (pin "1") (pinfunction "1_1") (pintype "passive"))
      (node (ref "R103") (pin "2") (pinfunction "2_2") (pintype "passive"))
      (node (ref "U2") (pin "4") (pinfunction "V-_4") (pintype "passive"))
    )
    (net (code "40") (name "Net-(U3A-IN+)") (class "Default")
      (node (ref "R25") (pin "2") (pinfunction "2_2") (pintype "passive"))
      (node (ref "R27") (pin "1") (pinfunction "1_1") (pintype "passive"))
      (node (ref "U3") (pin "8") (pinfunction "IN+_8") (pintype "passive"))
    )
    (net (code "41") (name "Net-(U3A-IN-)") (class "Default")
      (node (ref "R26") (pin "2") (pinfunction "2_2") (pintype "passive"))
      (node (ref "R28") (pin "1") (pinfunction "1_1") (pintype "passive"))
      (node (ref "U3") (pin "1") (pinfunction "IN-_1") (pintype "passive"))
    )
    (net (code "42") (name "Net-(U3A-OUT)") (class "Default")
      (node (ref "R28") (pin "2") (pinfunction "2_2") (pintype "passive"))
      (node (ref "R30") (pin "1") (pinfunction "1_1") (pintype "passive"))
      (node (ref "U3") (pin "4") (pinfunction "OUT_4") (pintype "passive"))
    )
    (net (code "43") (name "Net-(U3A-OUT+)") (class "Default")
      (node (ref "R27") (pin "2") (pinfunction "2_2") (pintype "passive"))
      (node (ref "R29") (pin "1") (pinfunction "1_1") (pintype "passive"))
      (node (ref "U3") (pin "5") (pinfunction "OUT+_5") (pintype "passive"))
    )
    (net (code "44") (name "Net-(U3B-V+)") (class "Default")
      (node (ref "C104") (pin "1") (pinfunction "1_1") (pintype "passive"))
      (node (ref "R104") (pin "1") (pinfunction "1_1") (pintype "passive"))
      (node (ref "U3") (pin "3") (pinfunction "V+_3") (pintype "passive"))
    )
    (net (code "45") (name "Net-(U3B-V-)") (class "Default")
      (node (ref "C105") (pin "1") (pinfunction "1_1") (pintype "passive"))
      (node (ref "R105") (pin "2") (pinfunction "2_2") (pintype "passive"))
      (node (ref "U3") (pin "6") (pinfunction "V-_6") (pintype "passive"))
    )
    (net (code "46") (name "Net-(U4A-D)") (class "Default")
      (node (ref "R20") (pin "2") (pinfunction "2_2") (pintype "passive"))
      (node (ref "U4") (pin "1") (pinfunction "D_1") (pintype "passive"))
    )
    (net (code "47") (name "Net-(U4B-VDD)") (class "Default")
      (node (ref "C108") (pin "2") (pinfunction "2_2") (pintype "passive"))
      (node (ref "R108") (pin "1") (pinfunction "1_1") (pintype "passive"))
      (node (ref "U4") (pin "5") (pinfunction "VDD_5") (pintype "passive"))
    )
    (net (code "48") (name "Net-(U5A-D)") (class "Default")
      (node (ref "R24") (pin "2") (pinfunction "2_2") (pintype "passive"))
      (node (ref "U5") (pin "1") (pinfunction "D_1") (pintype "passive"))
    )
    (net (code "49") (name "Net-(U5B-VDD)") (class "Default")
      (node (ref "C110") (pin "2") (pinfunction "2_2") (pintype "passive"))
      (node (ref "R110") (pin "1") (pinfunction "1_1") (pintype "passive"))
      (node (ref "U5") (pin "5") (pinfunction "VDD_5") (pintype "passive"))
    )
    (net (code "50") (name "Net-(U7A-IN+)") (class "Default")
      (node (ref "C24") (pin "2") (pinfunction "2_2") (pintype "passive"))
      (node (ref "R45") (pin "1") (pinfunction "1_1") (pintype "passive"))
      (node (ref "R47") (pin "2") (pinfunction "2_2") (pintype "passive"))
      (node (ref "U7") (pin "3") (pinfunction "IN+_3") (pintype "passive"))
    )
    (net (code "51") (name "Net-(U7A-IN-)") (class "Default")
      (node (ref "C25") (pin "1") (pinfunction "1_1") (pintype "passive"))
      (node (ref "R44") (pin "1") (pinfunction "1_1") (pintype "passive"))
      (node (ref "R46") (pin "1") (pinfunction "1_1") (pintype "passive"))
      (node (ref "U7") (pin "2") (pinfunction "IN-_2") (pintype "passive"))
    )
    (net (code "52") (name "Net-(U7A-OUT)") (class "Default")
      (node (ref "R71") (pin "1") (pinfunction "1_1") (pintype "passive"))
      (node (ref "U7") (pin "6") (pinfunction "OUT_6") (pintype "passive"))
    )
    (net (code "53") (name "Net-(U7B-V+)") (class "Default")
      (node (ref "C200") (pin "2") (pinfunction "2_2") (pintype "passive"))
      (node (ref "R200") (pin "1") (pinfunction "1_1") (pintype "passive"))
      (node (ref "U7") (pin "7") (pinfunction "V+_7") (pintype "passive"))
    )
    (net (code "54") (name "Net-(U7B-V-)") (class "Default")
      (node (ref "C201") (pin "2") (pinfunction "2_2") (pintype "passive"))
      (node (ref "R201") (pin "2") (pinfunction "2_2") (pintype "passive"))
      (node (ref "U7") (pin "4") (pinfunction "V-_4") (pintype "passive"))
    )
    (net (code "55") (name "Net-(U8A-IN+)") (class "Default")
      (node (ref "R57") (pin "1") (pinfunction "1_1") (pintype "passive"))
      (node (ref "U8") (pin "3") (pinfunction "IN+_3") (pintype "passive"))
    )
    (net (code "56") (name "Net-(U8A-IN-)") (class "Default")
      (node (ref "R58") (pin "2") (pinfunction "2_2") (pintype "passive"))
      (node (ref "U8") (pin "2") (pinfunction "IN-_2") (pintype "passive"))
    )
    (net (code "57") (name "Net-(U8B-IN-)") (class "Default")
      (node (ref "R62") (pin "2") (pinfunction "2_2") (pintype "passive"))
      (node (ref "R63") (pin "1") (pinfunction "1_1") (pintype "passive"))
      (node (ref "R64") (pin "1") (pinfunction "1_1") (pintype "passive"))
      (node (ref "U8") (pin "6") (pinfunction "IN-_6") (pintype "passive"))
    )
    (net (code "58") (name "Net-(U8C-V+)") (class "Default")
      (node (ref "C202") (pin "1") (pinfunction "1_1") (pintype "passive"))
      (node (ref "R202") (pin "1") (pinfunction "1_1") (pintype "passive"))
      (node (ref "U8") (pin "8") (pinfunction "V+_8") (pintype "passive"))
    )
    (net (code "59") (name "Net-(U8C-V-)") (class "Default")
      (node (ref "C203") (pin "1") (pinfunction "1_1") (pintype "passive"))
      (node (ref "R203") (pin "2") (pinfunction "2_2") (pintype "passive"))
      (node (ref "U8") (pin "4") (pinfunction "V-_4") (pintype "passive"))
    )
    (net (code "60") (name "Net-(U9A-IN+)") (class "Default")
      (node (ref "R65") (pin "2") (pinfunction "2_2") (pintype "passive"))
      (node (ref "R67") (pin "1") (pinfunction "1_1") (pintype "passive"))
      (node (ref "U9") (pin "8") (pinfunction "IN+_8") (pintype "passive"))
    )
    (net (code "61") (name "Net-(U9A-IN-)") (class "Default")
      (node (ref "R66") (pin "2") (pinfunction "2_2") (pintype "passive"))
      (node (ref "R68") (pin "1") (pinfunction "1_1") (pintype "passive"))
      (node (ref "U9") (pin "1") (pinfunction "IN-_1") (pintype "passive"))
    )
    (net (code "62") (name "Net-(U9A-OUT)") (class "Default")
      (node (ref "R68") (pin "2") (pinfunction "2_2") (pintype "passive"))
      (node (ref "R70") (pin "1") (pinfunction "1_1") (pintype "passive"))
      (node (ref "U9") (pin "4") (pinfunction "OUT_4") (pintype "passive"))
    )
    (net (code "63") (name "Net-(U9A-OUT+)") (class "Default")
      (node (ref "R67") (pin "2") (pinfunction "2_2") (pintype "passive"))
      (node (ref "R69") (pin "1") (pinfunction "1_1") (pintype "passive"))
      (node (ref "U9") (pin "5") (pinfunction "OUT+_5") (pintype "passive"))
    )
    (net (code "64") (name "Net-(U9B-V+)") (class "Default")
      (node (ref "C204") (pin "1") (pinfunction "1_1") (pintype "passive"))
      (node (ref "R204") (pin "1") (pinfunction "1_1") (pintype "passive"))
      (node (ref "U9") (pin "3") (pinfunction "V+_3") (pintype "passive"))
    )
    (net (code "65") (name "Net-(U9B-V-)") (class "Default")
      (node (ref "C205") (pin "1") (pinfunction "1_1") (pintype "passive"))
      (node (ref "R205") (pin "2") (pinfunction "2_2") (pintype "passive"))
      (node (ref "U9") (pin "6") (pinfunction "V-_6") (pintype "passive"))
    )
    (net (code "66") (name "Net-(U10A-D)") (class "Default")
      (node (ref "R60") (pin "2") (pinfunction "2_2") (pintype "passive"))
      (node (ref "U10") (pin "1") (pinfunction "D_1") (pintype "passive"))
    )
    (net (code "67") (name "Net-(U10A-S)") (class "Default")
      (node (ref "C28") (pin "1") (pinfunction "1_1") (pintype "passive"))
      (node (ref "R59") (pin "2") (pinfunction "2_2") (pintype "passive"))
      (node (ref "U10") (pin "2") (pinfunction "S_2") (pintype "passive"))
      (node (ref "U8") (pin "1") (pinfunction "OUT_1") (pintype "passive"))
    )
    (net (code "68") (name "Net-(U10B-VDD)") (class "Default")
      (node (ref "C208") (pin "2") (pinfunction "2_2") (pintype "passive"))
      (node (ref "R208") (pin "1") (pinfunction "1_1") (pintype "passive"))
      (node (ref "U10") (pin "5") (pinfunction "VDD_5") (pintype "passive"))
    )
    (net (code "69") (name "Net-(U11A-D)") (class "Default")
      (node (ref "R64") (pin "2") (pinfunction "2_2") (pintype "passive"))
      (node (ref "U11") (pin "1") (pinfunction "D_1") (pintype "passive"))
    )
    (net (code "70") (name "Net-(U11A-S)") (class "Default")
      (node (ref "R63") (pin "2") (pinfunction "2_2") (pintype "passive"))
      (node (ref "R65") (pin "1") (pinfunction "1_1") (pintype "passive"))
      (node (ref "U11") (pin "2") (pinfunction "S_2") (pintype "passive"))
      (node (ref "U8") (pin "7") (pinfunction "OUT_7") (pintype "passive"))
    )
    (net (code "71") (name "Net-(U11B-VDD)") (class "Default")
      (node (ref "C210") (pin "2") (pinfunction "2_2") (pintype "passive"))
      (node (ref "R210") (pin "1") (pinfunction "1_1") (pintype "passive"))
      (node (ref "U11") (pin "5") (pinfunction "VDD_5") (pintype "passive"))
    )
    (net (code "72") (name "Net-(U20A-IN-)") (class "Default")
      (node (ref "R31") (pin "2") (pinfunction "2_2") (pintype "passive"))
      (node (ref "R32") (pin "1") (pinfunction "1_1") (pintype "passive"))
      (node (ref "U20") (pin "4") (pinfunction "IN-_4") (pintype "input"))
    )
    (net (code "73") (name "Net-(U20A-OUT)") (class "Default")
      (node (ref "C1") (pin "2") (pinfunction "2_2") (pintype "passive"))
      (node (ref "C6") (pin "2") (pinfunction "2_2") (pintype "passive"))
      (node (ref "R32") (pin "2") (pinfunction "2_2") (pintype "passive"))
      (node (ref "U20") (pin "1") (pinfunction "OUT_1") (pintype "output"))
    )
    (net (code "74") (name "Net-(U20B-GND)") (class "Default")
      (node (ref "C112") (pin "2") (pinfunction "2_2") (pintype "passive"))
      (node (ref "R112") (pin "2") (pinfunction "2_2") (pintype "passive"))
      (node (ref "U20") (pin "2") (pinfunction "GND_2") (pintype "passive"))
    )
    (net (code "75") (name "Net-(U20B-VDD)") (class "Default")
      (node (ref "C111") (pin "2") (pinfunction "2_2") (pintype "passive"))
      (node (ref "R111") (pin "1") (pinfunction "1_1") (pintype "passive"))
      (node (ref "U20") (pin "5") (pinfunction "VDD_5") (pintype "passive"))
    )
    (net (code "76") (name "Net-(U21A-IN-)") (class "Default")
      (node (ref "R71") (pin "2") (pinfunction "2_2") (pintype "passive"))
      (node (ref "R72") (pin "1") (pinfunction "1_1") (pintype "passive"))
      (node (ref "U21") (pin "4") (pinfunction "IN-_4") (pintype "input"))
    )
    (net (code "77") (name "Net-(U21A-OUT)") (class "Default")
      (node (ref "C21") (pin "1") (pinfunction "1_1") (pintype "passive"))
      (node (ref "C26") (pin "1") (pinfunction "1_1") (pintype "passive"))
      (node (ref "R72") (pin "2") (pinfunction "2_2") (pintype "passive"))
      (node (ref "U21") (pin "1") (pinfunction "OUT_1") (pintype "output"))
    )
    (net (code "78") (name "Net-(U21B-GND)") (class "Default")
      (node (ref "C212") (pin "2") (pinfunction "2_2") (pintype "passive"))
      (node (ref "R212") (pin "2") (pinfunction "2_2") (pintype "passive"))
      (node (ref "U21") (pin "2") (pinfunction "GND_2") (pintype "passive"))
    )
    (net (code "79") (name "Net-(U21B-VDD)") (class "Default")
      (node (ref "C211") (pin "2") (pinfunction "2_2") (pintype "passive"))
      (node (ref "R211") (pin "1") (pinfunction "1_1") (pintype "passive"))
      (node (ref "U21") (pin "5") (pinfunction "VDD_5") (pintype "passive"))
    )
    (net (code "80") (name "unconnected-(U1-Pad8)") (class "Default")
      (node (ref "U1") (pin "8") (pinfunction "8_8") (pintype "passive"))
    )
    (net (code "81") (name "unconnected-(U7-Pad8)") (class "Default")
      (node (ref "U7") (pin "8") (pinfunction "8_8") (pintype "passive"))
    )
  )
)
